# adapter.net
KiCad netlist of a schematic drawn in EAGLE
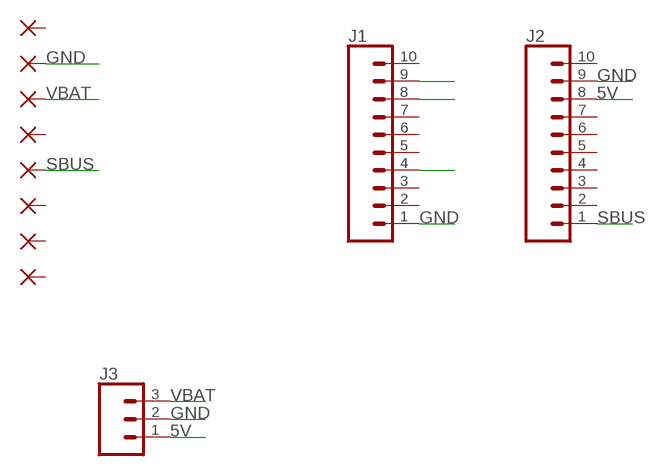
[diagram p0: schematic, sheet 1]

(export (version "E")
  (design (tool "Eeschema 10.0.6"))
  (components
    (comp (ref "GND")
      (value "SMD2")
      (footprint "eagle-import:SMD1,27-2,54")
      (libsource (lib "eagle-import") (part "SMD2"))
    )
    (comp (ref "J1")
      (value "CONN_10NO_SILK_PTH_FEMALE")
      (footprint "eagle-import:1X10_NO_SILK")
      (libsource (lib "eagle-import") (part "CONN_10NO_SILK_PTH_FEMALE"))
    )
    (comp (ref "J2")
      (value "CONN_10NO_SILK_PTH_FEMALE")
      (footprint "eagle-import:1X10_NO_SILK")
      (libsource (lib "eagle-import") (part "CONN_10NO_SILK_PTH_FEMALE"))
    )
    (comp (ref "J3")
      (value "CONN_031X03_NO_SILK")
      (footprint "eagle-import:1X03_NO_SILK")
      (libsource (lib "eagle-import") (part "CONN_031X03_NO_SILK"))
    )
    (comp (ref "PAD1")
      (value "SMD2")
      (footprint "eagle-import:SMD1,27-2,54")
      (libsource (lib "eagle-import") (part "SMD2"))
    )
    (comp (ref "PAD2")
      (value "SMD2")
      (footprint "eagle-import:SMD1,27-2,54")
      (libsource (lib "eagle-import") (part "SMD2"))
    )
    (comp (ref "PAD3")
      (value "SMD2")
      (footprint "eagle-import:SMD1,27-2,54")
      (libsource (lib "eagle-import") (part "SMD2"))
    )
    (comp (ref "PAD4")
      (value "SMD2")
      (footprint "eagle-import:SMD1,27-2,54")
      (libsource (lib "eagle-import") (part "SMD2"))
    )
    (comp (ref "PAD5")
      (value "SMD2")
      (footprint "eagle-import:SMD1,27-2,54")
      (libsource (lib "eagle-import") (part "SMD2"))
    )
    (comp (ref "SBUS")
      (value "SMD2")
      (footprint "eagle-import:SMD1,27-2,54")
      (libsource (lib "eagle-import") (part "SMD2"))
    )
    (comp (ref "VBAT")
      (value "SMD2")
      (footprint "eagle-import:SMD1,27-2,54")
      (libsource (lib "eagle-import") (part "SMD2"))
    )
  )
  (nets
    (net (code "1") (name "/5V") (class "Default")
      (node (ref "J2") (pin "8") (pinfunction "8_8") (pintype "passive"))
      (node (ref "J3") (pin "1") (pinfunction "1_1") (pintype "passive"))
    )
    (net (code "2") (name "/GND") (class "Default")
      (node (ref "GND") (pin "1") (pinfunction "P_1") (pintype "passive"))
      (node (ref "J1") (pin "1") (pinfunction "1_1") (pintype "passive"))
      (node (ref "J2") (pin "9") (pinfunction "9_9") (pintype "passive"))
      (node (ref "J3") (pin "2") (pinfunction "2_2") (pintype "passive"))
    )
    (net (code "3") (name "/SBUS") (class "Default")
      (node (ref "J2") (pin "1") (pinfunction "1_1") (pintype "passive"))
      (node (ref "SBUS") (pin "1") (pinfunction "P_1") (pintype "passive"))
    )
    (net (code "4") (name "/VBAT") (class "Default")
      (node (ref "J3") (pin "3") (pinfunction "3_3") (pintype "passive"))
      (node (ref "VBAT") (pin "1") (pinfunction "P_1") (pintype "passive"))
    )
    (net (code "5") (name "unconnected-(J1-Pad2)") (class "Default")
      (node (ref "J1") (pin "2") (pinfunction "2_2") (pintype "passive"))
    )
    (net (code "6") (name "unconnected-(J1-Pad3)") (class "Default")
      (node (ref "J1") (pin "3") (pinfunction "3_3") (pintype "passive"))
    )
    (net (code "7") (name "unconnected-(J1-Pad4)") (class "Default")
      (node (ref "J1") (pin "4") (pinfunction "4_4") (pintype "passive"))
    )
    (net (code "8") (name "unconnected-(J1-Pad5)") (class "Default")
      (node (ref "J1") (pin "5") (pinfunction "5_5") (pintype "passive"))
    )
    (net (code "9") (name "unconnected-(J1-Pad6)") (class "Default")
      (node (ref "J1") (pin "6") (pinfunction "6_6") (pintype "passive"))
    )
    (net (code "10") (name "unconnected-(J1-Pad7)") (class "Default")
      (node (ref "J1") (pin "7") (pinfunction "7_7") (pintype "passive"))
    )
    (net (code "11") (name "unconnected-(J1-Pad8)") (class "Default")
      (node (ref "J1") (pin "8") (pinfunction "8_8") (pintype "passive"))
    )
    (net (code "12") (name "unconnected-(J1-Pad9)") (class "Default")
      (node (ref "J1") (pin "9") (pinfunction "9_9") (pintype "passive"))
    )
    (net (code "13") (name "unconnected-(J1-Pad10)") (class "Default")
      (node (ref "J1") (pin "10") (pinfunction "10_10") (pintype "passive"))
    )
    (net (code "14") (name "unconnected-(J2-Pad2)") (class "Default")
      (node (ref "J2") (pin "2") (pinfunction "2_2") (pintype "passive"))
    )
    (net (code "15") (name "unconnected-(J2-Pad3)") (class "Default")
      (node (ref "J2") (pin "3") (pinfunction "3_3") (pintype "passive"))
    )
    (net (code "16") (name "unconnected-(J2-Pad4)") (class "Default")
      (node (ref "J2") (pin "4") (pinfunction "4_4") (pintype "passive"))
    )
    (net (code "17") (name "unconnected-(J2-Pad5)") (class "Default")
      (node (ref "J2") (pin "5") (pinfunction "5_5") (pintype "passive"))
    )
    (net (code "18") (name "unconnected-(J2-Pad6)") (class "Default")
      (node (ref "J2") (pin "6") (pinfunction "6_6") (pintype "passive"))
    )
    (net (code "19") (name "unconnected-(J2-Pad7)") (class "Default")
      (node (ref "J2") (pin "7") (pinfunction "7_7") (pintype "passive"))
    )
    (net (code "20") (name "unconnected-(J2-Pad10)") (class "Default")
      (node (ref "J2") (pin "10") (pinfunction "10_10") (pintype "passive"))
    )
    (net (code "21") (name "unconnected-(PAD1-P-Pad1)") (class "Default")
      (node (ref "PAD1") (pin "1") (pinfunction "P_1") (pintype "passive"))
    )
    (net (code "22") (name "unconnected-(PAD2-P-Pad1)") (class "Default")
      (node (ref "PAD2") (pin "1") (pinfunction "P_1") (pintype "passive"))
    )
    (net (code "23") (name "unconnected-(PAD3-P-Pad1)") (class "Default")
      (node (ref "PAD3") (pin "1") (pinfunction "P_1") (pintype "passive"))
    )
    (net (code "24") (name "unconnected-(PAD4-P-Pad1)") (class "Default")
      (node (ref "PAD4") (pin "1") (pinfunction "P_1") (pintype "passive"))
    )
    (net (code "25") (name "unconnected-(PAD5-P-Pad1)") (class "Default")
      (node (ref "PAD5") (pin "1") (pinfunction "P_1") (pintype "passive"))
    )
  )
)
